# MultiWiiChassis_hexlite_power.net
KiCad netlist of a schematic drawn in EAGLE
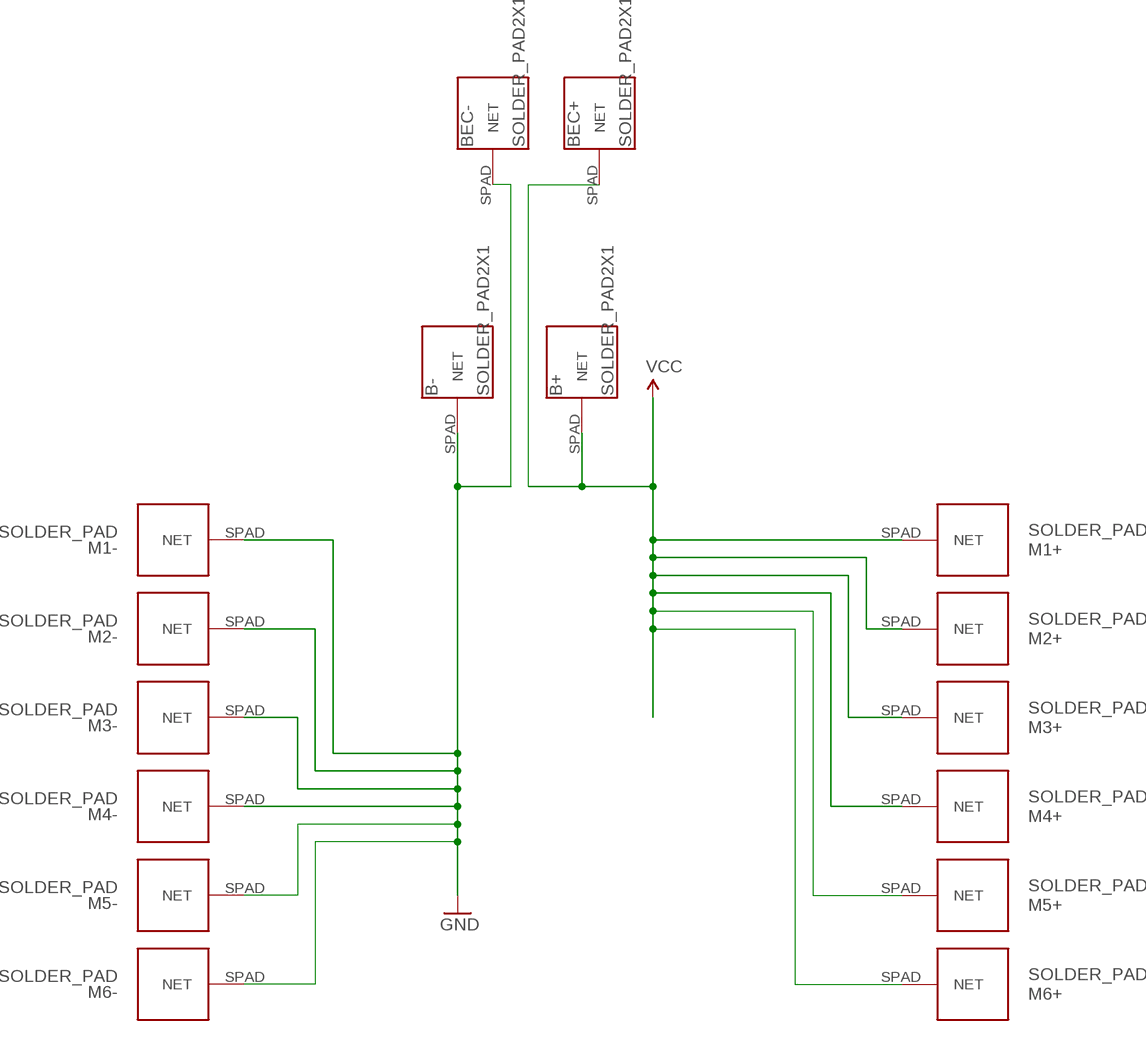
[diagram p0: schematic, sheet 1]

(export (version "E")
  (design (tool "Eeschema 10.0.6"))
  (components
    (comp (ref "B+")
      (value "SOLDER_PAD2X1")
      (footprint "eagle-import:SOLDER_PAD_2X1")
      (libsource (lib "eagle-import") (part "SOLDER_PAD2X1"))
    )
    (comp (ref "B-")
      (value "SOLDER_PAD2X1")
      (footprint "eagle-import:SOLDER_PAD_2X1")
      (libsource (lib "eagle-import") (part "SOLDER_PAD2X1"))
    )
    (comp (ref "BEC+")
      (value "SOLDER_PAD2X1")
      (footprint "eagle-import:SOLDER_PAD_2X1")
      (libsource (lib "eagle-import") (part "SOLDER_PAD2X1"))
    )
    (comp (ref "BEC-")
      (value "SOLDER_PAD2X1")
      (footprint "eagle-import:SOLDER_PAD_2X1")
      (libsource (lib "eagle-import") (part "SOLDER_PAD2X1"))
    )
    (comp (ref "M1+")
      (value "SOLDER_PAD")
      (footprint "eagle-import:SOLDER_PAD")
      (libsource (lib "eagle-import") (part "SOLDER_PAD"))
    )
    (comp (ref "M1-")
      (value "SOLDER_PAD")
      (footprint "eagle-import:SOLDER_PAD")
      (libsource (lib "eagle-import") (part "SOLDER_PAD"))
    )
    (comp (ref "M2+")
      (value "SOLDER_PAD")
      (footprint "eagle-import:SOLDER_PAD")
      (libsource (lib "eagle-import") (part "SOLDER_PAD"))
    )
    (comp (ref "M2-")
      (value "SOLDER_PAD")
      (footprint "eagle-import:SOLDER_PAD")
      (libsource (lib "eagle-import") (part "SOLDER_PAD"))
    )
    (comp (ref "M3+")
      (value "SOLDER_PAD")
      (footprint "eagle-import:SOLDER_PAD")
      (libsource (lib "eagle-import") (part "SOLDER_PAD"))
    )
    (comp (ref "M3-")
      (value "SOLDER_PAD")
      (footprint "eagle-import:SOLDER_PAD")
      (libsource (lib "eagle-import") (part "SOLDER_PAD"))
    )
    (comp (ref "M4+")
      (value "SOLDER_PAD")
      (footprint "eagle-import:SOLDER_PAD")
      (libsource (lib "eagle-import") (part "SOLDER_PAD"))
    )
    (comp (ref "M4-")
      (value "SOLDER_PAD")
      (footprint "eagle-import:SOLDER_PAD")
      (libsource (lib "eagle-import") (part "SOLDER_PAD"))
    )
    (comp (ref "M5+")
      (value "SOLDER_PAD")
      (footprint "eagle-import:SOLDER_PAD")
      (libsource (lib "eagle-import") (part "SOLDER_PAD"))
    )
    (comp (ref "M5-")
      (value "SOLDER_PAD")
      (footprint "eagle-import:SOLDER_PAD")
      (libsource (lib "eagle-import") (part "SOLDER_PAD"))
    )
    (comp (ref "M6+")
      (value "SOLDER_PAD")
      (footprint "eagle-import:SOLDER_PAD")
      (libsource (lib "eagle-import") (part "SOLDER_PAD"))
    )
    (comp (ref "M6-")
      (value "SOLDER_PAD")
      (footprint "eagle-import:SOLDER_PAD")
      (libsource (lib "eagle-import") (part "SOLDER_PAD"))
    )
  )
  (nets
    (net (code "1") (name "GND") (class "Default")
      (node (ref "B-") (pin "SPAD") (pinfunction "NET_SPAD") (pintype "bidirectional"))
      (node (ref "BEC-") (pin "SPAD") (pinfunction "NET_SPAD") (pintype "bidirectional"))
      (node (ref "M1-") (pin "SPAD") (pinfunction "NET_SPAD") (pintype "bidirectional"))
      (node (ref "M2-") (pin "SPAD") (pinfunction "NET_SPAD") (pintype "bidirectional"))
      (node (ref "M3-") (pin "SPAD") (pinfunction "NET_SPAD") (pintype "bidirectional"))
      (node (ref "M4-") (pin "SPAD") (pinfunction "NET_SPAD") (pintype "bidirectional"))
      (node (ref "M5-") (pin "SPAD") (pinfunction "NET_SPAD") (pintype "bidirectional"))
      (node (ref "M6-") (pin "SPAD") (pinfunction "NET_SPAD") (pintype "bidirectional"))
    )
    (net (code "2") (name "VCC") (class "Default")
      (node (ref "B+") (pin "SPAD") (pinfunction "NET_SPAD") (pintype "bidirectional"))
      (node (ref "BEC+") (pin "SPAD") (pinfunction "NET_SPAD") (pintype "bidirectional"))
      (node (ref "M1+") (pin "SPAD") (pinfunction "NET_SPAD") (pintype "bidirectional"))
      (node (ref "M2+") (pin "SPAD") (pinfunction "NET_SPAD") (pintype "bidirectional"))
      (node (ref "M3+") (pin "SPAD") (pinfunction "NET_SPAD") (pintype "bidirectional"))
      (node (ref "M4+") (pin "SPAD") (pinfunction "NET_SPAD") (pintype "bidirectional"))
      (node (ref "M5+") (pin "SPAD") (pinfunction "NET_SPAD") (pintype "bidirectional"))
      (node (ref "M6+") (pin "SPAD") (pinfunction "NET_SPAD") (pintype "bidirectional"))
    )
  )
)
